# Domino_Pi_No_Teardrop.net
KiCad netlist of a schematic drawn in EAGLE
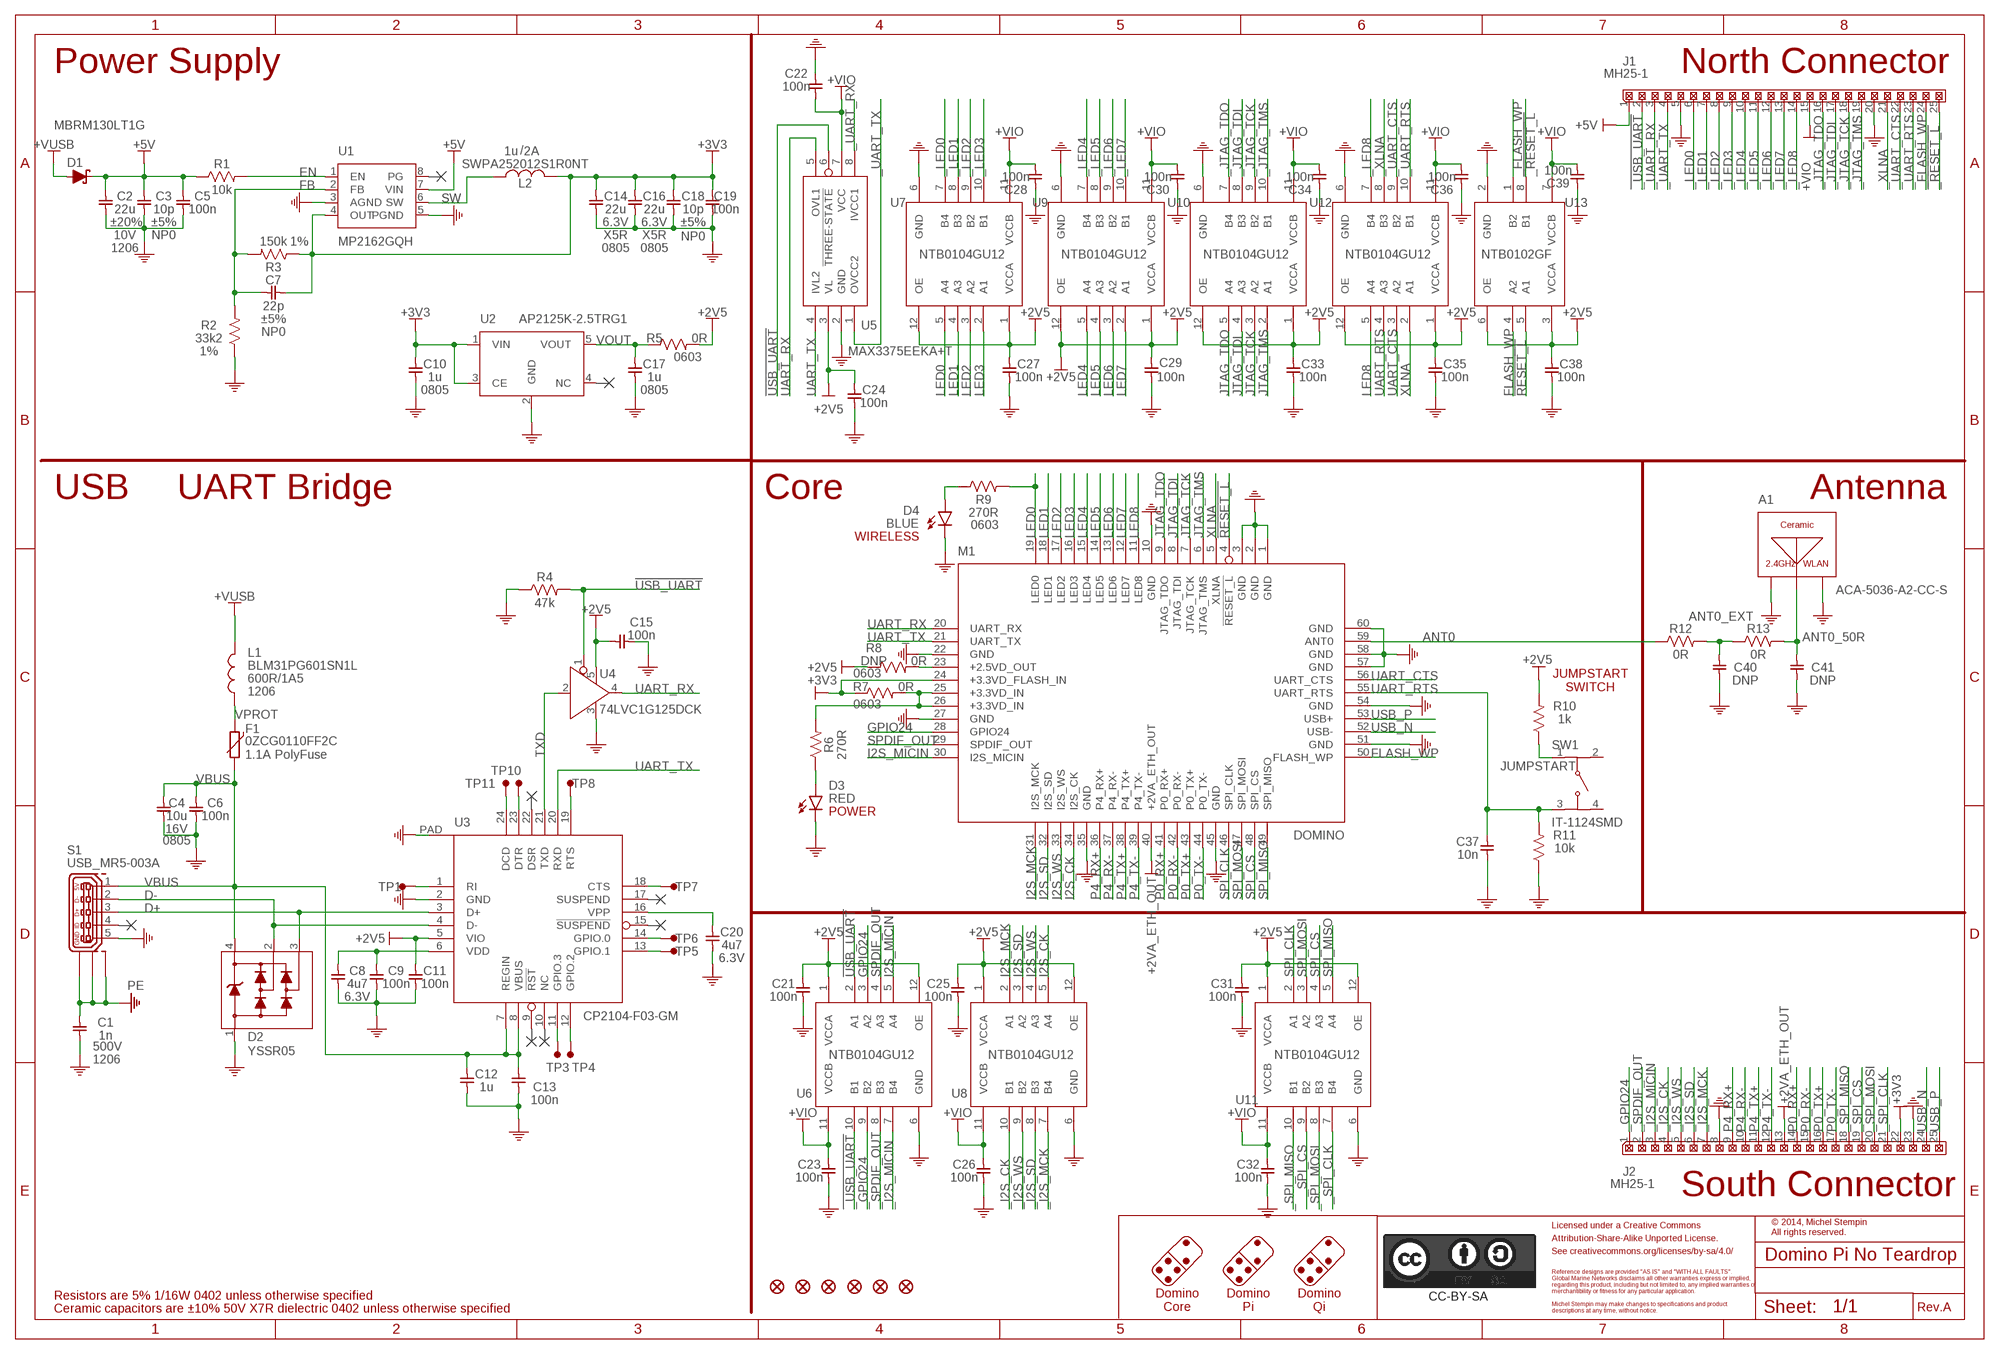
[diagram p0: schematic, sheet 1]

(export (version "E")
  (design (tool "Eeschema 10.0.6"))
  (components
    (comp (ref "A1")
      (value "ACA-5036-A2-CC-S")
      (footprint "eagle-import:ACA-5036-A2-CC-S")
      (libsource (lib "eagle-import") (part "ACA-5036-A2-CC-S"))
    )
    (comp (ref "C1")
      (value "1n")
      (footprint "eagle-import:C1206")
      (fields
        (field (name "SIZE") "1206")
        (field (name "PARTNO") "C1206_1n_X7R_10%_CER_500V")
        (field (name "VOLT") "500V")
      )
      (libsource (lib "eagle-import") (part "CAP_1206"))
    )
    (comp (ref "C2")
      (value "22u")
      (footprint "eagle-import:C1206")
      (fields
        (field (name "SIZE") "1206")
        (field (name "PARTNO") "C1206_22u_X7R_20%_CER_10V")
        (field (name "TOL") "±20%")
        (field (name "VOLT") "10V")
      )
      (libsource (lib "eagle-import") (part "CAP_1206"))
    )
    (comp (ref "C3")
      (value "10p")
      (footprint "eagle-import:C0402")
      (fields
        (field (name "PARTNO") "C0402_10p_NP0_5%_CER_50V")
        (field (name "TC") "NP0")
        (field (name "TOL") "±5%")
      )
      (libsource (lib "eagle-import") (part "CAP_0402"))
    )
    (comp (ref "C4")
      (value "10u")
      (footprint "eagle-import:C0805")
      (fields
        (field (name "SIZE") "0805")
        (field (name "PARTNO") "C0805_10u_X7R_10%_CER_16V")
        (field (name "VOLT") "16V")
      )
      (libsource (lib "eagle-import") (part "CAP_0805"))
    )
    (comp (ref "C5")
      (value "100n")
      (footprint "eagle-import:C0402")
      (fields (field (name "PARTNO") "C0402_100n_X7R_10%_CER_50V"))
      (libsource (lib "eagle-import") (part "CAP_0402"))
    )
    (comp (ref "C6")
      (value "100n")
      (footprint "eagle-import:C0402")
      (fields (field (name "PARTNO") "C0402_100n_X7R_10%_CER_50V"))
      (libsource (lib "eagle-import") (part "CAP_0402"))
    )
    (comp (ref "C7")
      (value "22p")
      (footprint "eagle-import:C0402")
      (fields
        (field (name "PARTNO") "C0402_22p_NP0_5%_CER_50V")
        (field (name "TC") "NP0")
        (field (name "TOL") "±5%")
      )
      (libsource (lib "eagle-import") (part "CAP_0402"))
    )
    (comp (ref "C8")
      (value "4u7")
      (footprint "eagle-import:C0402")
      (fields (field (name "PARTNO") "C0402_4u7_X7R_10%_CER_6V3") (field (name "VOLT") "6.3V"))
      (libsource (lib "eagle-import") (part "CAP_0402"))
    )
    (comp (ref "C9")
      (value "100n")
      (footprint "eagle-import:C0402")
      (fields (field (name "PARTNO") "C0402_100n_X7R_10%_CER_50V"))
      (libsource (lib "eagle-import") (part "CAP_0402"))
    )
    (comp (ref "C10")
      (value "1u")
      (footprint "eagle-import:C0805")
      (fields (field (name "SIZE") "0805") (field (name "PARTNO") "C0805_1u_X7R_10%_CER_50V"))
      (libsource (lib "eagle-import") (part "CAP_0805"))
    )
    (comp (ref "C11")
      (value "100n")
      (footprint "eagle-import:C0402")
      (fields (field (name "PARTNO") "C0402_100n_X7R_10%_CER_50V"))
      (libsource (lib "eagle-import") (part "CAP_0402"))
    )
    (comp (ref "C12")
      (value "1u")
      (footprint "eagle-import:C0402")
      (fields (field (name "PARTNO") "C0402_1u_X7R_10%_CER_50V"))
      (libsource (lib "eagle-import") (part "CAP_0402"))
    )
    (comp (ref "C13")
      (value "100n")
      (footprint "eagle-import:C0402")
      (fields (field (name "PARTNO") "C0402_100n_X7R_10%_CER_50V"))
      (libsource (lib "eagle-import") (part "CAP_0402"))
    )
    (comp (ref "C14")
      (value "22u")
      (footprint "eagle-import:C0805")
      (fields
        (field (name "SIZE") "0805")
        (field (name "PARTNO") "C0805_22u_X5R_20%_CER_6V3")
        (field (name "TC") "X5R")
        (field (name "VOLT") "6.3V")
      )
      (libsource (lib "eagle-import") (part "CAP_0805"))
    )
    (comp (ref "C15")
      (value "100n")
      (footprint "eagle-import:C0402")
      (fields (field (name "PARTNO") "C0402_100n_X7R_10%_CER_50V"))
      (libsource (lib "eagle-import") (part "CAP_0402"))
    )
    (comp (ref "C16")
      (value "22u")
      (footprint "eagle-import:C0805")
      (fields
        (field (name "SIZE") "0805")
        (field (name "PARTNO") "C0805_22u_X5R_20%_CER_6V3")
        (field (name "TC") "X5R")
        (field (name "VOLT") "6.3V")
      )
      (libsource (lib "eagle-import") (part "CAP_0805"))
    )
    (comp (ref "C17")
      (value "1u")
      (footprint "eagle-import:C0805")
      (fields (field (name "SIZE") "0805") (field (name "PARTNO") "C0805_1u_X7R_10%_CER_50V"))
      (libsource (lib "eagle-import") (part "CAP_0805"))
    )
    (comp (ref "C18")
      (value "10p")
      (footprint "eagle-import:C0402")
      (fields
        (field (name "PARTNO") "C0402_10p_NP0_5%_CER_50V")
        (field (name "TC") "NP0")
        (field (name "TOL") "±5%")
      )
      (libsource (lib "eagle-import") (part "CAP_0402"))
    )
    (comp (ref "C19")
      (value "100n")
      (footprint "eagle-import:C0402")
      (fields (field (name "PARTNO") "C0402_100n_X7R_10%_CER_50V"))
      (libsource (lib "eagle-import") (part "CAP_0402"))
    )
    (comp (ref "C20")
      (value "4u7")
      (footprint "eagle-import:C0402")
      (fields (field (name "PARTNO") "C0402_4u7_X7R_10%_CER_6V3") (field (name "VOLT") "6.3V"))
      (libsource (lib "eagle-import") (part "CAP_0402"))
    )
    (comp (ref "C21")
      (value "100n")
      (footprint "eagle-import:C0402")
      (fields (field (name "PARTNO") "C0402_100n_X7R_10%_CER_50V"))
      (libsource (lib "eagle-import") (part "CAP_0402"))
    )
    (comp (ref "C22")
      (value "100n")
      (footprint "eagle-import:C0402")
      (fields (field (name "PARTNO") "C0402_100n_X7R_10%_CER_50V"))
      (libsource (lib "eagle-import") (part "CAP_0402"))
    )
    (comp (ref "C23")
      (value "100n")
      (footprint "eagle-import:C0402")
      (fields (field (name "PARTNO") "C0402_100n_X7R_10%_CER_50V"))
      (libsource (lib "eagle-import") (part "CAP_0402"))
    )
    (comp (ref "C24")
      (value "100n")
      (footprint "eagle-import:C0402")
      (fields (field (name "PARTNO") "C0402_100n_X7R_10%_CER_50V"))
      (libsource (lib "eagle-import") (part "CAP_0402"))
    )
    (comp (ref "C25")
      (value "100n")
      (footprint "eagle-import:C0402")
      (fields (field (name "PARTNO") "C0402_100n_X7R_10%_CER_50V"))
      (libsource (lib "eagle-import") (part "CAP_0402"))
    )
    (comp (ref "C26")
      (value "100n")
      (footprint "eagle-import:C0402")
      (fields (field (name "PARTNO") "C0402_100n_X7R_10%_CER_50V"))
      (libsource (lib "eagle-import") (part "CAP_0402"))
    )
    (comp (ref "C27")
      (value "100n")
      (footprint "eagle-import:C0402")
      (fields (field (name "PARTNO") "C0402_100n_X7R_10%_CER_50V"))
      (libsource (lib "eagle-import") (part "CAP_0402"))
    )
    (comp (ref "C28")
      (value "100n")
      (footprint "eagle-import:C0402")
      (fields (field (name "PARTNO") "C0402_100n_X7R_10%_CER_50V"))
      (libsource (lib "eagle-import") (part "CAP_0402"))
    )
    (comp (ref "C29")
      (value "100n")
      (footprint "eagle-import:C0402")
      (fields (field (name "PARTNO") "C0402_100n_X7R_10%_CER_50V"))
      (libsource (lib "eagle-import") (part "CAP_0402"))
    )
    (comp (ref "C30")
      (value "100n")
      (footprint "eagle-import:C0402")
      (fields (field (name "PARTNO") "C0402_100n_X7R_10%_CER_50V"))
      (libsource (lib "eagle-import") (part "CAP_0402"))
    )
    (comp (ref "C31")
      (value "100n")
      (footprint "eagle-import:C0402")
      (fields (field (name "PARTNO") "C0402_100n_X7R_10%_CER_50V"))
      (libsource (lib "eagle-import") (part "CAP_0402"))
    )
    (comp (ref "C32")
      (value "100n")
      (footprint "eagle-import:C0402")
      (fields (field (name "PARTNO") "C0402_100n_X7R_10%_CER_50V"))
      (libsource (lib "eagle-import") (part "CAP_0402"))
    )
    (comp (ref "C33")
      (value "100n")
      (footprint "eagle-import:C0402")
      (fields (field (name "PARTNO") "C0402_100n_X7R_10%_CER_50V"))
      (libsource (lib "eagle-import") (part "CAP_0402"))
    )
    (comp (ref "C34")
      (value "100n")
      (footprint "eagle-import:C0402")
      (fields (field (name "PARTNO") "C0402_100n_X7R_10%_CER_50V"))
      (libsource (lib "eagle-import") (part "CAP_0402"))
    )
    (comp (ref "C35")
      (value "100n")
      (footprint "eagle-import:C0402")
      (fields (field (name "PARTNO") "C0402_100n_X7R_10%_CER_50V"))
      (libsource (lib "eagle-import") (part "CAP_0402"))
    )
    (comp (ref "C36")
      (value "100n")
      (footprint "eagle-import:C0402")
      (fields (field (name "PARTNO") "C0402_100n_X7R_10%_CER_50V"))
      (libsource (lib "eagle-import") (part "CAP_0402"))
    )
    (comp (ref "C37")
      (value "10n")
      (footprint "eagle-import:C0402")
      (fields (field (name "PARTNO") "C0402_10n_X7R_10%_CER_50V"))
      (libsource (lib "eagle-import") (part "CAP_0402"))
    )
    (comp (ref "C38")
      (value "100n")
      (footprint "eagle-import:C0402")
      (fields (field (name "PARTNO") "C0402_100n_X7R_10%_CER_50V"))
      (libsource (lib "eagle-import") (part "CAP_0402"))
    )
    (comp (ref "C39")
      (value "100n")
      (footprint "eagle-import:C0402")
      (fields (field (name "PARTNO") "C0402_100n_X7R_10%_CER_50V"))
      (libsource (lib "eagle-import") (part "CAP_0402"))
    )
    (comp (ref "C40")
      (value "DNP")
      (footprint "eagle-import:C0402")
      (fields (field (name "PARTNO") "C0402_DNP"))
      (libsource (lib "eagle-import") (part "CAP_0402"))
    )
    (comp (ref "C41")
      (value "DNP")
      (footprint "eagle-import:C0402")
      (fields (field (name "PARTNO") "C0402_DNP"))
      (libsource (lib "eagle-import") (part "CAP_0402"))
    )
    (comp (ref "CC-BY-SA")
      (value "CC-BY-SA_LOGO")
      (footprint "eagle-import:CC-BY-SA_LOGO")
      (libsource (lib "eagle-import") (part "CC-BY-SA_LOGO"))
    )
    (comp (ref "D1")
      (value "MBRM130LT1G")
      (footprint "eagle-import:DO-216AA")
      (libsource (lib "eagle-import") (part "MBRM130LT1G"))
    )
    (comp (ref "D2")
      (value "YSSR05")
      (footprint "eagle-import:SOT143B")
      (libsource (lib "eagle-import") (part "YSSR05"))
    )
    (comp (ref "D3")
      (value "RED")
      (footprint "eagle-import:LED0603")
      (fields (field (name "PARTNO") "LED0603-RED"))
      (libsource (lib "eagle-import") (part "LED_0603"))
    )
    (comp (ref "D4")
      (value "BLUE")
      (footprint "eagle-import:LED0603")
      (fields (field (name "PARTNO") "LED0603-BLUE"))
      (libsource (lib "eagle-import") (part "LED_0603"))
    )
    (comp (ref "F1")
      (value "0ZCG0110FF2C")
      (footprint "eagle-import:PTC1812")
      (fields (field (name "RATE") "1.1A"))
      (libsource (lib "eagle-import") (part "0ZCG0110FF2C"))
    )
    (comp (ref "F2")
      (value "FIDUCIAL")
      (footprint "eagle-import:FIDUCIAL")
      (libsource (lib "eagle-import") (part "FIDUCIAL"))
    )
    (comp (ref "F3")
      (value "FIDUCIAL")
      (footprint "eagle-import:FIDUCIAL")
      (libsource (lib "eagle-import") (part "FIDUCIAL"))
    )
    (comp (ref "F4")
      (value "FIDUCIAL")
      (footprint "eagle-import:FIDUCIAL")
      (libsource (lib "eagle-import") (part "FIDUCIAL"))
    )
    (comp (ref "F5")
      (value "FIDUCIAL")
      (footprint "eagle-import:FIDUCIAL")
      (libsource (lib "eagle-import") (part "FIDUCIAL"))
    )
    (comp (ref "F6")
      (value "FIDUCIAL")
      (footprint "eagle-import:FIDUCIAL")
      (libsource (lib "eagle-import") (part "FIDUCIAL"))
    )
    (comp (ref "F7")
      (value "FIDUCIAL")
      (footprint "eagle-import:FIDUCIAL")
      (libsource (lib "eagle-import") (part "FIDUCIAL"))
    )
    (comp (ref "J1")
      (value "MH25-1")
      (footprint "eagle-import:MH25-1-0.1")
      (fields (field (name "PARTNO") "MH25-1-0.1"))
      (libsource (lib "eagle-import") (part "MH25-1"))
    )
    (comp (ref "J2")
      (value "MH25-1")
      (footprint "eagle-import:MH25-1-0.1")
      (fields (field (name "PARTNO") "MH25-1-0.1"))
      (libsource (lib "eagle-import") (part "MH25-1"))
    )
    (comp (ref "L1")
      (value "BLM31PG601SN1L")
      (footprint "eagle-import:FB1206")
      (fields (field (name "SIZE") "1206") (field (name "OPT") "600R/1A5"))
      (libsource (lib "eagle-import") (part "FB_1206"))
    )
    (comp (ref "L2")
      (value "SWPA252012S1R0NT")
      (footprint "eagle-import:SWPA252012S")
      (fields
        (field (name "INDUCTANCE") "1u")
        (field (name "RATE") "2A")
        (field (name "PARTNO") "SWPA252012SMT")
        (field (name "RATE_1") "2A")
      )
      (libsource (lib "eagle-import") (part "SWPA252012S?NT1R0"))
    )
    (comp (ref "M1")
      (value "DOMINO")
      (footprint "eagle-import:DOMINO")
      (fields (field (name "PARTNO") "DOMINO-CORE"))
      (libsource (lib "eagle-import") (part "DOMINO"))
    )
    (comp (ref "R1")
      (value "10k")
      (footprint "eagle-import:R0402")
      (fields (field (name "PARTNO") "R0402_10k_5%_62.5mW"))
      (libsource (lib "eagle-import") (part "RES_0402"))
    )
    (comp (ref "R2")
      (value "33k2")
      (footprint "eagle-import:R0402")
      (fields (field (name "PARTNO") "R0402_33k2_1%_62.5mW") (field (name "TOL") "1%"))
      (libsource (lib "eagle-import") (part "RES_0402"))
    )
    (comp (ref "R3")
      (value "150k")
      (footprint "eagle-import:R0402")
      (fields (field (name "PARTNO") "R0402_150k_1%_62.5mW") (field (name "TOL") "1%"))
      (libsource (lib "eagle-import") (part "RES_0402"))
    )
    (comp (ref "R4")
      (value "47k")
      (footprint "eagle-import:R0402")
      (fields (field (name "PARTNO") "R0402_47k_5%_62.5mW"))
      (libsource (lib "eagle-import") (part "RES_0402"))
    )
    (comp (ref "R5")
      (value "0R")
      (footprint "eagle-import:R0603")
      (fields (field (name "SIZE") "0603") (field (name "PARTNO") "R0603_0R_5%_125mW"))
      (libsource (lib "eagle-import") (part "RES_0603"))
    )
    (comp (ref "R6")
      (value "270R")
      (footprint "eagle-import:R0402")
      (fields (field (name "PARTNO") "R0603_270R_5%_125mW"))
      (libsource (lib "eagle-import") (part "RES_0402"))
    )
    (comp (ref "R7")
      (value "0R")
      (footprint "eagle-import:R0603")
      (fields (field (name "SIZE") "0603") (field (name "PARTNO") "R0603_0R_5%_125mW"))
      (libsource (lib "eagle-import") (part "RES_0603"))
    )
    (comp (ref "R8")
      (value "0R")
      (footprint "eagle-import:R0603")
      (fields (field (name "SIZE") "0603") (field (name "PARTNO") "R0603_0R_5%_125mW"))
      (libsource (lib "eagle-import") (part "RES_0603"))
    )
    (comp (ref "R9")
      (value "270R")
      (footprint "eagle-import:R0603")
      (fields (field (name "SIZE") "0603") (field (name "PARTNO") "R0603_270R_5%_125mW"))
      (libsource (lib "eagle-import") (part "RES_0603"))
    )
    (comp (ref "R10")
      (value "1k")
      (footprint "eagle-import:R0402")
      (fields (field (name "PARTNO") "R0402_1k_5%_62.5mW"))
      (libsource (lib "eagle-import") (part "RES_0402"))
    )
    (comp (ref "R11")
      (value "10k")
      (footprint "eagle-import:R0402")
      (fields (field (name "PARTNO") "R0402_10k_5%_62.5mW"))
      (libsource (lib "eagle-import") (part "RES_0402"))
    )
    (comp (ref "R12")
      (value "0R")
      (footprint "eagle-import:R0402")
      (fields (field (name "PARTNO") "R0402_0R_5%_62.5mW"))
      (libsource (lib "eagle-import") (part "RES_0402"))
    )
    (comp (ref "R13")
      (value "0R")
      (footprint "eagle-import:R0402")
      (fields (field (name "PARTNO") "R0402_0R_5%_62.5mW"))
      (libsource (lib "eagle-import") (part "RES_0402"))
    )
    (comp (ref "S1")
      (value "USB_MR5-003A")
      (footprint "eagle-import:USB_MR5-003A")
      (fields (field (name "PARTNO") "USB MR5-003A"))
      (libsource (lib "eagle-import") (part "USB_MR5-003A"))
    )
    (comp (ref "SW1")
      (value "IT-1124SMD")
      (footprint "eagle-import:IT-1124SMD")
      (libsource (lib "eagle-import") (part "IT-1124SMD"))
    )
    (comp (ref "TP1")
      (value "TEST_PAD")
      (footprint "eagle-import:TEST_PAD")
      (libsource (lib "eagle-import") (part "TEST_PAD"))
    )
    (comp (ref "TP3")
      (value "TEST_PAD")
      (footprint "eagle-import:TEST_PAD")
      (libsource (lib "eagle-import") (part "TEST_PAD"))
    )
    (comp (ref "TP4")
      (value "TEST_PAD")
      (footprint "eagle-import:TEST_PAD")
      (libsource (lib "eagle-import") (part "TEST_PAD"))
    )
    (comp (ref "TP5")
      (value "TEST_PAD")
      (footprint "eagle-import:TEST_PAD")
      (libsource (lib "eagle-import") (part "TEST_PAD"))
    )
    (comp (ref "TP6")
      (value "TEST_PAD")
      (footprint "eagle-import:TEST_PAD")
      (libsource (lib "eagle-import") (part "TEST_PAD"))
    )
    (comp (ref "TP7")
      (value "TEST_PAD")
      (footprint "eagle-import:TEST_PAD")
      (libsource (lib "eagle-import") (part "TEST_PAD"))
    )
    (comp (ref "TP8")
      (value "TEST_PAD")
      (footprint "eagle-import:TEST_PAD")
      (libsource (lib "eagle-import") (part "TEST_PAD"))
    )
    (comp (ref "TP10")
      (value "TEST_PAD")
      (footprint "eagle-import:TEST_PAD")
      (libsource (lib "eagle-import") (part "TEST_PAD"))
    )
    (comp (ref "TP11")
      (value "TEST_PAD")
      (footprint "eagle-import:TEST_PAD")
      (libsource (lib "eagle-import") (part "TEST_PAD"))
    )
    (comp (ref "U1")
      (value "MP2162GQH")
      (footprint "eagle-import:QFN-8_2X1.5")
      (libsource (lib "eagle-import") (part "MP2162GQH"))
    )
    (comp (ref "U2")
      (value "AP2125K-2.5TRG1")
      (footprint "eagle-import:SOT23-5")
      (libsource (lib "eagle-import") (part "AP2125?K-2.5TRG1"))
    )
    (comp (ref "U3")
      (value "CP2104-F03-GM")
      (footprint "eagle-import:QFN-25_4X4")
      (libsource (lib "eagle-import") (part "CP2104-F03-GM"))
    )
    (comp (ref "U4")
      (value "74LVC1G125DCK")
      (footprint "eagle-import:SC70")
      (fields (field (name "PARTNO") "74LVC1G125DCK "))
      (libsource (lib "eagle-import") (part "741G125DCKLVC"))
    )
    (comp (ref "U5")
      (value "MAX3375EEKA+T")
      (footprint "eagle-import:SOT23-8")
      (libsource (lib "eagle-import") (part "MAX3375EEKA+T"))
    )
    (comp (ref "U6")
      (value "NTB0104GU12")
      (footprint "eagle-import:XQFN-12")
      (libsource (lib "eagle-import") (part "NTB0104GU12"))
    )
    (comp (ref "U7")
      (value "NTB0104GU12")
      (footprint "eagle-import:XQFN-12")
      (libsource (lib "eagle-import") (part "NTB0104GU12"))
    )
    (comp (ref "U8")
      (value "NTB0104GU12")
      (footprint "eagle-import:XQFN-12")
      (libsource (lib "eagle-import") (part "NTB0104GU12"))
    )
    (comp (ref "U9")
      (value "NTB0104GU12")
      (footprint "eagle-import:XQFN-12")
      (libsource (lib "eagle-import") (part "NTB0104GU12"))
    )
    (comp (ref "U10")
      (value "NTB0104GU12")
      (footprint "eagle-import:XQFN-12")
      (libsource (lib "eagle-import") (part "NTB0104GU12"))
    )
    (comp (ref "U11")
      (value "NTB0104GU12")
      (footprint "eagle-import:XQFN-12")
      (libsource (lib "eagle-import") (part "NTB0104GU12"))
    )
    (comp (ref "U12")
      (value "NTB0104GU12")
      (footprint "eagle-import:XQFN-12")
      (libsource (lib "eagle-import") (part "NTB0104GU12"))
    )
    (comp (ref "U13")
      (value "NTB0102GF")
      (footprint "eagle-import:SOT1089")
      (libsource (lib "eagle-import") (part "NTB0102GF"))
    )
  )
  (nets
    (net (code "1") (name "+2V5") (class "Default")
      (node (ref "C11") (pin "1") (pinfunction "1_1") (pintype "passive"))
      (node (ref "C15") (pin "2") (pinfunction "2_2") (pintype "passive"))
      (node (ref "C21") (pin "1") (pinfunction "1_1") (pintype "passive"))
      (node (ref "C24") (pin "2") (pinfunction "2_2") (pintype "passive"))
      (node (ref "C25") (pin "1") (pinfunction "1_1") (pintype "passive"))
      (node (ref "C27") (pin "2") (pinfunction "2_2") (pintype "passive"))
      (node (ref "C29") (pin "2") (pinfunction "2_2") (pintype "passive"))
      (node (ref "C31") (pin "1") (pinfunction "1_1") (pintype "passive"))
      (node (ref "C33") (pin "2") (pinfunction "2_2") (pintype "passive"))
      (node (ref "C35") (pin "2") (pinfunction "2_2") (pintype "passive"))
      (node (ref "C38") (pin "2") (pinfunction "2_2") (pintype "passive"))
      (node (ref "R10") (pin "2") (pinfunction "2_2") (pintype "passive"))
      (node (ref "R5") (pin "2") (pinfunction "2_2") (pintype "passive"))
      (node (ref "R8") (pin "1") (pinfunction "1_1") (pintype "passive"))
      (node (ref "U10") (pin "1") (pinfunction "VCCA_1") (pintype "power_in"))
      (node (ref "U10") (pin "12") (pinfunction "OE_12") (pintype "input"))
      (node (ref "U11") (pin "1") (pinfunction "VCCA_1") (pintype "power_in"))
      (node (ref "U11") (pin "12") (pinfunction "OE_12") (pintype "input"))
      (node (ref "U12") (pin "1") (pinfunction "VCCA_1") (pintype "power_in"))
      (node (ref "U12") (pin "12") (pinfunction "OE_12") (pintype "input"))
      (node (ref "U13") (pin "3") (pinfunction "VCCA_3") (pintype "power_in"))
      (node (ref "U13") (pin "6") (pinfunction "OE_6") (pintype "input"))
      (node (ref "U3") (pin "5") (pinfunction "VIO_5") (pintype "power_in"))
      (node (ref "U4") (pin "5") (pinfunction "VCC_5") (pintype "power_in"))
      (node (ref "U5") (pin "3") (pinfunction "VL_3") (pintype "power_in"))
      (node (ref "U6") (pin "1") (pinfunction "VCCA_1") (pintype "power_in"))
      (node (ref "U6") (pin "12") (pinfunction "OE_12") (pintype "input"))
      (node (ref "U7") (pin "1") (pinfunction "VCCA_1") (pintype "power_in"))
      (node (ref "U7") (pin "12") (pinfunction "OE_12") (pintype "input"))
      (node (ref "U8") (pin "1") (pinfunction "VCCA_1") (pintype "power_in"))
      (node (ref "U8") (pin "12") (pinfunction "OE_12") (pintype "input"))
      (node (ref "U9") (pin "1") (pinfunction "VCCA_1") (pintype "power_in"))
      (node (ref "U9") (pin "12") (pinfunction "OE_12") (pintype "input"))
    )
    (net (code "2") (name "+2VA_ETH_OUT") (class "Default")
      (node (ref "J2") (pin "13") (pinfunction "13_13") (pintype "passive"))
      (node (ref "M1") (pin "40") (pinfunction "+2VA_ETH_OUT_40") (pintype "power_in"))
    )
    (net (code "3") (name "+3V3") (class "Default")
      (node (ref "C10") (pin "1") (pinfunction "1_1") (pintype "passive"))
      (node (ref "C14") (pin "1") (pinfunction "1_1") (pintype "passive"))
      (node (ref "C16") (pin "1") (pinfunction "1_1") (pintype "passive"))
      (node (ref "C18") (pin "1") (pinfunction "1_1") (pintype "passive"))
      (node (ref "C19") (pin "1") (pinfunction "1_1") (pintype "passive"))
      (node (ref "C7") (pin "2") (pinfunction "2_2") (pintype "passive"))
      (node (ref "J2") (pin "22") (pinfunction "22_22") (pintype "passive"))
      (node (ref "L2") (pin "2") (pinfunction "2_2") (pintype "passive"))
      (node (ref "M1") (pin "24") (pinfunction "+3.3VD_FLASH_IN_24") (pintype "power_in"))
      (node (ref "R3") (pin "1") (pinfunction "1_1") (pintype "passive"))
      (node (ref "R7") (pin "1") (pinfunction "1_1") (pintype "passive"))
      (node (ref "U1") (pin "4") (pinfunction "OUT_4") (pintype "power_in"))
      (node (ref "U2") (pin "1") (pinfunction "VIN_1") (pintype "power_in"))
      (node (ref "U2") (pin "3") (pinfunction "CE_3") (pintype "input"))
    )
    (net (code "4") (name "+5V") (class "Default")
      (node (ref "C2") (pin "1") (pinfunction "1_1") (pintype "passive"))
      (node (ref "C3") (pin "1") (pinfunction "1_1") (pintype "passive"))
      (node (ref "C5") (pin "1") (pinfunction "1_1") (pintype "passive"))
      (node (ref "D1") (pin "1") (pinfunction "C_1") (pintype "passive"))
      (node (ref "J1") (pin "1") (pinfunction "1_1") (pintype "passive"))
      (node (ref "R1") (pin "1") (pinfunction "1_1") (pintype "passive"))
      (node (ref "U1") (pin "7") (pinfunction "VIN_7") (pintype "power_in"))
    )
    (net (code "5") (name "+VIO") (class "Default")
      (node (ref "C22") (pin "1") (pinfunction "1_1") (pintype "passive"))
      (node (ref "C23") (pin "1") (pinfunction "1_1") (pintype "passive"))
      (node (ref "C26") (pin "1") (pinfunction "1_1") (pintype "passive"))
      (node (ref "C28") (pin "1") (pinfunction "1_1") (pintype "passive"))
      (node (ref "C30") (pin "1") (pinfunction "1_1") (pintype "passive"))
      (node (ref "C32") (pin "1") (pinfunction "1_1") (pintype "passive"))
      (node (ref "C34") (pin "1") (pinfunction "1_1") (pintype "passive"))
      (node (ref "C36") (pin "1") (pinfunction "1_1") (pintype "passive"))
      (node (ref "C39") (pin "1") (pinfunction "1_1") (pintype "passive"))
      (node (ref "J1") (pin "15") (pinfunction "15_15") (pintype "passive"))
      (node (ref "U10") (pin "11") (pinfunction "VCCB_11") (pintype "power_in"))
      (node (ref "U11") (pin "11") (pinfunction "VCCB_11") (pintype "power_in"))
      (node (ref "U12") (pin "11") (pinfunction "VCCB_11") (pintype "power_in"))
      (node (ref "U13") (pin "7") (pinfunction "VCCB_7") (pintype "power_in"))
      (node (ref "U5") (pin "7") (pinfunction "VCC_7") (pintype "power_in"))
      (node (ref "U6") (pin "11") (pinfunction "VCCB_11") (pintype "power_in"))
      (node (ref "U7") (pin "11") (pinfunction "VCCB_11") (pintype "power_in"))
      (node (ref "U8") (pin "11") (pinfunction "VCCB_11") (pintype "power_in"))
      (node (ref "U9") (pin "11") (pinfunction "VCCB_11") (pintype "power_in"))
    )
    (net (code "6") (name "+VUSB") (class "Default")
      (node (ref "D1") (pin "2") (pinfunction "A_2") (pintype "passive"))
      (node (ref "L1") (pin "1") (pinfunction "1_1") (pintype "passive"))
    )
    (net (code "7") (name "/ANT0") (class "Default")
      (node (ref "M1") (pin "59") (pinfunction "ANT0_59") (pintype "passive"))
      (node (ref "R12") (pin "1") (pinfunction "1_1") (pintype "passive"))
    )
    (net (code "8") (name "/ANT0_50R") (class "Default")
      (node (ref "A1") (pin "FEED") (pinfunction "A_FEED") (pintype "passive"))
      (node (ref "C41") (pin "1") (pinfunction "1_1") (pintype "passive"))
      (node (ref "R13") (pin "2") (pinfunction "2_2") (pintype "passive"))
    )
    (net (code "9") (name "/ANT0_EXT") (class "Default")
      (node (ref "C40") (pin "1") (pinfunction "1_1") (pintype "passive"))
      (node (ref "R12") (pin "2") (pinfunction "2_2") (pintype "passive"))
      (node (ref "R13") (pin "1") (pinfunction "1_1") (pintype "passive"))
    )
    (net (code "10") (name "/D+") (class "Default")
      (node (ref "D2") (pin "3") (pinfunction "P$3_3") (pintype "passive"))
      (node (ref "S1") (pin "3") (pinfunction "3_3") (pintype "passive"))
      (node (ref "U3") (pin "3") (pinfunction "D+_3") (pintype "passive"))
    )
    (net (code "11") (name "/D-") (class "Default")
      (node (ref "D2") (pin "2") (pinfunction "P$2_2") (pintype "passive"))
      (node (ref "S1") (pin "2") (pinfunction "2_2") (pintype "passive"))
      (node (ref "U3") (pin "4") (pinfunction "D-_4") (pintype "passive"))
    )
    (net (code "12") (name "/EN") (class "Default")
      (node (ref "R1") (pin "2") (pinfunction "2_2") (pintype "passive"))
      (node (ref "U1") (pin "1") (pinfunction "EN_1") (pintype "input"))
    )
    (net (code "13") (name "/FB") (class "Default")
      (node (ref "C7") (pin "1") (pinfunction "1_1") (pintype "passive"))
      (node (ref "R2") (pin "2") (pinfunction "2_2") (pintype "passive"))
      (node (ref "R3") (pin "2") (pinfunction "2_2") (pintype "passive"))
      (node (ref "U1") (pin "2") (pinfunction "FB_2") (pintype "passive"))
    )
    (net (code "14") (name "/FLASH_WP") (class "Default")
      (node (ref "M1") (pin "50") (pinfunction "FLASH_WP_50") (pintype "bidirectional"))
      (node (ref "U13") (pin "4") (pinfunction "A2_4") (pintype "bidirectional"))
    )
    (net (code "15") (name "/GPIO24") (class "Default")
      (node (ref "M1") (pin "28") (pinfunction "GPIO24_28") (pintype "bidirectional"))
      (node (ref "U6") (pin "3") (pinfunction "A2_3") (pintype "bidirectional"))
    )
    (net (code "16") (name "/I2S_CK") (class "Default")
      (node (ref "M1") (pin "34") (pinfunction "I2S_CK_34") (pintype "bidirectional"))
      (node (ref "U8") (pin "5") (pinfunction "A4_5") (pintype "bidirectional"))
    )
    (net (code "17") (name "/I2S_MCK") (class "Default")
      (node (ref "M1") (pin "31") (pinfunction "I2S_MCK_31") (pintype "bidirectional"))
      (node (ref "U8") (pin "2") (pinfunction "A1_2") (pintype "bidirectional"))
    )
    (net (code "18") (name "/I2S_MICIN") (class "Default")
      (node (ref "M1") (pin "30") (pinfunction "I2S_MICIN_30") (pintype "bidirectional"))
      (node (ref "U6") (pin "5") (pinfunction "A4_5") (pintype "bidirectional"))
    )
    (net (code "19") (name "/I2S_SD") (class "Default")
      (node (ref "M1") (pin "32") (pinfunction "I2S_SD_32") (pintype "bidirectional"))
      (node (ref "U8") (pin "3") (pinfunction "A2_3") (pintype "bidirectional"))
    )
    (net (code "20") (name "/I2S_WS") (class "Default")
      (node (ref "M1") (pin "33") (pinfunction "I2S_WS_33") (pintype "bidirectional"))
      (node (ref "U8") (pin "4") (pinfunction "A3_4") (pintype "bidirectional"))
    )
    (net (code "21") (name "/JTAG_TCK") (class "Default")
      (node (ref "M1") (pin "7") (pinfunction "JTAG_TCK_7") (pintype "bidirectional"))
      (node (ref "U10") (pin "3") (pinfunction "A2_3") (pintype "bidirectional"))
    )
    (net (code "22") (name "/JTAG_TDI") (class "Default")
      (node (ref "M1") (pin "8") (pinfunction "JTAG_TDI_8") (pintype "bidirectional"))
      (node (ref "U10") (pin "4") (pinfunction "A3_4") (pintype "bidirectional"))
    )
    (net (code "23") (name "/JTAG_TDO") (class "Default")
      (node (ref "M1") (pin "9") (pinfunction "JTAG_TDO_9") (pintype "bidirectional"))
      (node (ref "U10") (pin "5") (pinfunction "A4_5") (pintype "bidirectional"))
    )
    (net (code "24") (name "/JTAG_TMS") (class "Default")
      (node (ref "M1") (pin "6") (pinfunction "JTAG_TMS_6") (pintype "bidirectional"))
      (node (ref "U10") (pin "2") (pinfunction "A1_2") (pintype "bidirectional"))
    )
    (net (code "25") (name "/JUMPSTART") (class "Default")
      (node (ref "R10") (pin "1") (pinfunction "1_1") (pintype "passive"))
      (node (ref "SW1") (pin "1") (pinfunction "1_1") (pintype "passive"))
    )
    (net (code "26") (name "/LED0") (class "Default")
      (node (ref "M1") (pin "19") (pinfunction "LED0_19") (pintype "bidirectional"))
      (node (ref "R9") (pin "2") (pinfunction "2_2") (pintype "passive"))
      (node (ref "U7") (pin "5") (pinfunction "A4_5") (pintype "bidirectional"))
    )
    (net (code "27") (name "/LED1") (class "Default")
      (node (ref "M1") (pin "18") (pinfunction "LED1_18") (pintype "bidirectional"))
      (node (ref "U7") (pin "4") (pinfunction "A3_4") (pintype "bidirectional"))
    )
    (net (code "28") (name "/LED2") (class "Default")
      (node (ref "M1") (pin "17") (pinfunction "LED2_17") (pintype "bidirectional"))
      (node (ref "U7") (pin "3") (pinfunction "A2_3") (pintype "bidirectional"))
    )
    (net (code "29") (name "/LED3") (class "Default")
      (node (ref "M1") (pin "16") (pinfunction "LED3_16") (pintype "bidirectional"))
      (node (ref "U7") (pin "2") (pinfunction "A1_2") (pintype "bidirectional"))
    )
    (net (code "30") (name "/LED4") (class "Default")
      (node (ref "M1") (pin "15") (pinfunction "LED4_15") (pintype "bidirectional"))
      (node (ref "U9") (pin "5") (pinfunction "A4_5") (pintype "bidirectional"))
    )
    (net (code "31") (name "/LED5") (class "Default")
      (node (ref "M1") (pin "14") (pinfunction "LED5_14") (pintype "bidirectional"))
      (node (ref "U9") (pin "4") (pinfunction "A3_4") (pintype "bidirectional"))
    )
    (net (code "32") (name "/LED6") (class "Default")
      (node (ref "M1") (pin "13") (pinfunction "LED6_13") (pintype "bidirectional"))
      (node (ref "U9") (pin "3") (pinfunction "A2_3") (pintype "bidirectional"))
    )
    (net (code "33") (name "/LED7") (class "Default")
      (node (ref "M1") (pin "12") (pinfunction "LED7_12") (pintype "bidirectional"))
      (node (ref "U9") (pin "2") (pinfunction "A1_2") (pintype "bidirectional"))
    )
    (net (code "34") (name "/LED8") (class "Default")
      (node (ref "M1") (pin "11") (pinfunction "LED8_11") (pintype "bidirectional"))
      (node (ref "U12") (pin "5") (pinfunction "A4_5") (pintype "bidirectional"))
    )
    (net (code "35") (name "/P0_RX+") (class "Default")
      (node (ref "J2") (pin "14") (pinfunction "14_14") (pintype "passive"))
      (node (ref "M1") (pin "41") (pinfunction "P0_RX+_41") (pintype "passive"))
    )
    (net (code "36") (name "/P0_RX-") (class "Default")
      (node (ref "J2") (pin "15") (pinfunction "15_15") (pintype "passive"))
      (node (ref "M1") (pin "42") (pinfunction "P0_RX-_42") (pintype "passive"))
    )
    (net (code "37") (name "/P0_TX+") (class "Default")
      (node (ref "J2") (pin "16") (pinfunction "16_16") (pintype "passive"))
      (node (ref "M1") (pin "43") (pinfunction "P0_TX+_43") (pintype "passive"))
    )
    (net (code "38") (name "/P0_TX-") (class "Default")
      (node (ref "J2") (pin "17") (pinfunction "17_17") (pintype "passive"))
      (node (ref "M1") (pin "44") (pinfunction "P0_TX-_44") (pintype "passive"))
    )
    (net (code "39") (name "/P4_RX+") (class "Default")
      (node (ref "J2") (pin "9") (pinfunction "9_9") (pintype "passive"))
      (node (ref "M1") (pin "36") (pinfunction "P4_RX+_36") (pintype "passive"))
    )
    (net (code "40") (name "/P4_RX-") (class "Default")
      (node (ref "J2") (pin "10") (pinfunction "10_10") (pintype "passive"))
      (node (ref "M1") (pin "37") (pinfunction "P4_RX-_37") (pintype "passive"))
    )
    (net (code "41") (name "/P4_TX+") (class "Default")
      (node (ref "J2") (pin "11") (pinfunction "11_11") (pintype "passive"))
      (node (ref "M1") (pin "38") (pinfunction "P4_TX+_38") (pintype "passive"))
    )
    (net (code "42") (name "/P4_TX-") (class "Default")
      (node (ref "J2") (pin "12") (pinfunction "12_12") (pintype "passive"))
      (node (ref "M1") (pin "39") (pinfunction "P4_TX-_39") (pintype "passive"))
    )
    (net (code "43") (name "/SPDIF_OUT") (class "Default")
      (node (ref "M1") (pin "29") (pinfunction "SPDIF_OUT_29") (pintype "bidirectional"))
      (node (ref "U6") (pin "4") (pinfunction "A3_4") (pintype "bidirectional"))
    )
    (net (code "44") (name "/SPI_CLK") (class "Default")
      (node (ref "M1") (pin "46") (pinfunction "SPI_CLK_46") (pintype "bidirectional"))
      (node (ref "U11") (pin "2") (pinfunction "A1_2") (pintype "bidirectional"))
    )
    (net (code "45") (name "/SPI_CS") (class "Default")
      (node (ref "M1") (pin "48") (pinfunction "SPI_CS_48") (pintype "bidirectional"))
      (node (ref "U11") (pin "4") (pinfunction "A3_4") (pintype "bidirectional"))
    )
    (net (code "46") (name "/SPI_MISO") (class "Default")
      (node (ref "M1") (pin "49") (pinfunction "SPI_MISO_49") (pintype "bidirectional"))
      (node (ref "U11") (pin "5") (pinfunction "A4_5") (pintype "bidirectional"))
    )
    (net (code "47") (name "/SPI_MOSI") (class "Default")
      (node (ref "M1") (pin "47") (pinfunction "SPI_MOSI_47") (pintype "bidirectional"))
      (node (ref "U11") (pin "3") (pinfunction "A2_3") (pintype "bidirectional"))
    )
    (net (code "48") (name "/SW") (class "Default")
      (node (ref "L2") (pin "1") (pinfunction "1_1") (pintype "passive"))
      (node (ref "U1") (pin "6") (pinfunction "SW_6") (pintype "passive"))
    )
    (net (code "49") (name "/TXD") (class "Default")
      (node (ref "U3") (pin "21") (pinfunction "TXD_21") (pintype "output"))
      (node (ref "U4") (pin "2") (pinfunction "A_2") (pintype "input"))
    )
    (net (code "50") (name "/UART_CTS") (class "Default")
      (node (ref "M1") (pin "56") (pinfunction "UART_CTS_56") (pintype "bidirectional"))
      (node (ref "U12") (pin "3") (pinfunction "A2_3") (pintype "bidirectional"))
    )
    (net (code "51") (name "/UART_RTS") (class "Default")
      (node (ref "C37") (pin "1") (pinfunction "1_1") (pintype "passive"))
      (node (ref "M1") (pin "55") (pinfunction "UART_RTS_55") (pintype "bidirectional"))
      (node (ref "R11") (pin "2") (pinfunction "2_2") (pintype "passive"))
      (node (ref "SW1") (pin "3") (pinfunction "3_3") (pintype "passive"))
      (node (ref "U12") (pin "4") (pinfunction "A3_4") (pintype "bidirectional"))
    )
    (net (code "52") (name "/UART_RX") (class "Default")
      (node (ref "M1") (pin "20") (pinfunction "UART_RX_20") (pintype "bidirectional"))
      (node (ref "U4") (pin "4") (pinfunction "Y_4") (pintype "tri_state"))
      (node (ref "U5") (pin "5") (pinfunction "OVL1_5") (pintype "output"))
    )
    (net (code "53") (name "/UART_TX") (class "Default")
      (node (ref "M1") (pin "21") (pinfunction "UART_TX_21") (pintype "bidirectional"))
      (node (ref "U3") (pin "20") (pinfunction "RXD_20") (pintype "input"))
      (node (ref "U5") (pin "4") (pinfunction "IVL2_4") (pintype "input"))
    )
    (net (code "54") (name "/USB_N") (class "Default")
      (node (ref "J2") (pin "24") (pinfunction "24_24") (pintype "passive"))
      (node (ref "M1") (pin "52") (pinfunction "USB-_52") (pintype "passive"))
    )
    (net (code "55") (name "/USB_P") (class "Default")
      (node (ref "J2") (pin "25") (pinfunction "25_25") (pintype "passive"))
      (node (ref "M1") (pin "53") (pinfunction "USB+_53") (pintype "passive"))
    )
    (net (code "56") (name "/VBUS") (class "Default")
      (node (ref "C12") (pin "1") (pinfunction "1_1") (pintype "passive"))
      (node (ref "C13") (pin "1") (pinfunction "1_1") (pintype "passive"))
      (node (ref "C4") (pin "1") (pinfunction "1_1") (pintype "passive"))
      (node (ref "C6") (pin "1") (pinfunction "1_1") (pintype "passive"))
      (node (ref "D2") (pin "4") (pinfunction "P$4_4") (pintype "passive"))
      (node (ref "F1") (pin "2") (pinfunction "2_2") (pintype "passive"))
      (node (ref "S1") (pin "1") (pinfunction "1_1") (pintype "passive"))
      (node (ref "U3") (pin "7") (pinfunction "REGIN_7") (pintype "power_in"))
      (node (ref "U3") (pin "8") (pinfunction "VBUS_8") (pintype "input"))
    )
    (net (code "57") (name "/VOUT") (class "Default")
      (node (ref "C17") (pin "1") (pinfunction "1_1") (pintype "passive"))
      (node (ref "R5") (pin "1") (pinfunction "1_1") (pintype "passive"))
      (node (ref "U2") (pin "5") (pinfunction "VOUT_5") (pintype "power_in"))
    )
    (net (code "58") (name "/VPROT") (class "Default")
      (node (ref "F1") (pin "1") (pinfunction "1_1") (pintype "passive"))
      (node (ref "L1") (pin "2") (pinfunction "2_2") (pintype "passive"))
    )
    (net (code "59") (name "/XLNA") (class "Default")
      (node (ref "M1") (pin "5") (pinfunction "XLNA_5") (pintype "bidirectional"))
      (node (ref "U12") (pin "2") (pinfunction "A1_2") (pintype "bidirectional"))
    )
    (net (code "60") (name "/_FLASH_WP") (class "Default")
      (node (ref "J1") (pin "24") (pinfunction "24_24") (pintype "passive"))
      (node (ref "U13") (pin "1") (pinfunction "B2_1") (pintype "bidirectional"))
    )
    (net (code "61") (name "/_GPIO24") (class "Default")
      (node (ref "J2") (pin "1") (pinfunction "1_1") (pintype "passive"))
      (node (ref "U6") (pin "9") (pinfunction "B2_9") (pintype "bidirectional"))
    )
    (net (code "62") (name "/_I2S_CK") (class "Default")
      (node (ref "J2") (pin "4") (pinfunction "4_4") (pintype "passive"))
      (node (ref "U8") (pin "10") (pinfunction "B1_10") (pintype "bidirectional"))
    )
    (net (code "63") (name "/_I2S_MCK") (class "Default")
      (node (ref "J2") (pin "7") (pinfunction "7_7") (pintype "passive"))
      (node (ref "U8") (pin "7") (pinfunction "B4_7") (pintype "bidirectional"))
    )
    (net (code "64") (name "/_I2S_MICIN") (class "Default")
      (node (ref "J2") (pin "3") (pinfunction "3_3") (pintype "passive"))
      (node (ref "U6") (pin "7") (pinfunction "B4_7") (pintype "bidirectional"))
    )
    (net (code "65") (name "/_I2S_SD") (class "Default")
      (node (ref "J2") (pin "6") (pinfunction "6_6") (pintype "passive"))
      (node (ref "U8") (pin "8") (pinfunction "B3_8") (pintype "bidirectional"))
    )
    (net (code "66") (name "/_I2S_WS") (class "Default")
      (node (ref "J2") (pin "5") (pinfunction "5_5") (pintype "passive"))
      (node (ref "U8") (pin "9") (pinfunction "B2_9") (pintype "bidirectional"))
    )
    (net (code "67") (name "/_JTAG_TCK") (class "Default")
      (node (ref "J1") (pin "18") (pinfunction "18_18") (pintype "passive"))
      (node (ref "U10") (pin "9") (pinfunction "B2_9") (pintype "bidirectional"))
    )
    (net (code "68") (name "/_JTAG_TDI") (class "Default")
      (node (ref "J1") (pin "17") (pinfunction "17_17") (pintype "passive"))
      (node (ref "U10") (pin "8") (pinfunction "B3_8") (pintype "bidirectional"))
    )
    (net (code "69") (name "/_JTAG_TDO") (class "Default")
      (node (ref "J1") (pin "16") (pinfunction "16_16") (pintype "passive"))
      (node (ref "U10") (pin "7") (pinfunction "B4_7") (pintype "bidirectional"))
    )
    (net (code "70") (name "/_JTAG_TMS") (class "Default")
      (node (ref "J1") (pin "19") (pinfunction "19_19") (pintype "passive"))
      (node (ref "U10") (pin "10") (pinfunction "B1_10") (pintype "bidirectional"))
    )
    (net (code "71") (name "/_LED0") (class "Default")
      (node (ref "J1") (pin "6") (pinfunction "6_6") (pintype "passive"))
      (node (ref "U7") (pin "7") (pinfunction "B4_7") (pintype "bidirectional"))
    )
    (net (code "72") (name "/_LED1") (class "Default")
      (node (ref "J1") (pin "7") (pinfunction "7_7") (pintype "passive"))
      (node (ref "U7") (pin "8") (pinfunction "B3_8") (pintype "bidirectional"))
    )
    (net (code "73") (name "/_LED2") (class "Default")
      (node (ref "J1") (pin "8") (pinfunction "8_8") (pintype "passive"))
      (node (ref "U7") (pin "9") (pinfunction "B2_9") (pintype "bidirectional"))
    )
    (net (code "74") (name "/_LED3") (class "Default")
      (node (ref "J1") (pin "9") (pinfunction "9_9") (pintype "passive"))
      (node (ref "U7") (pin "10") (pinfunction "B1_10") (pintype "bidirectional"))
    )
    (net (code "75") (name "/_LED4") (class "Default")
      (node (ref "J1") (pin "10") (pinfunction "10_10") (pintype "passive"))
      (node (ref "U9") (pin "7") (pinfunction "B4_7") (pintype "bidirectional"))
    )
    (net (code "76") (name "/_LED5") (class "Default")
      (node (ref "J1") (pin "11") (pinfunction "11_11") (pintype "passive"))
      (node (ref "U9") (pin "8") (pinfunction "B3_8") (pintype "bidirectional"))
    )
    (net (code "77") (name "/_LED6") (class "Default")
      (node (ref "J1") (pin "12") (pinfunction "12_12") (pintype "passive"))
      (node (ref "U9") (pin "9") (pinfunction "B2_9") (pintype "bidirectional"))
    )
    (net (code "78") (name "/_LED7") (class "Default")
      (node (ref "J1") (pin "13") (pinfunction "13_13") (pintype "passive"))
      (node (ref "U9") (pin "10") (pinfunction "B1_10") (pintype "bidirectional"))
    )
    (net (code "79") (name "/_LED8") (class "Default")
      (node (ref "J1") (pin "14") (pinfunction "14_14") (pintype "passive"))
      (node (ref "U12") (pin "7") (pinfunction "B4_7") (pintype "bidirectional"))
    )
    (net (code "80") (name "/_SPDIF_OUT") (class "Default")
      (node (ref "J2") (pin "2") (pinfunction "2_2") (pintype "passive"))
      (node (ref "U6") (pin "8") (pinfunction "B3_8") (pintype "bidirectional"))
    )
    (net (code "81") (name "/_SPI_CLK") (class "Default")
      (node (ref "J2") (pin "21") (pinfunction "21_21") (pintype "passive"))
      (node (ref "U11") (pin "7") (pinfunction "B4_7") (pintype "bidirectional"))
    )
    (net (code "82") (name "/_SPI_CS") (class "Default")
      (node (ref "J2") (pin "19") (pinfunction "19_19") (pintype "passive"))
      (node (ref "U11") (pin "9") (pinfunction "B2_9") (pintype "bidirectional"))
    )
    (net (code "83") (name "/_SPI_MISO") (class "Default")
      (node (ref "J2") (pin "18") (pinfunction "18_18") (pintype "passive"))
      (node (ref "U11") (pin "10") (pinfunction "B1_10") (pintype "bidirectional"))
    )
    (net (code "84") (name "/_SPI_MOSI") (class "Default")
      (node (ref "J2") (pin "20") (pinfunction "20_20") (pintype "passive"))
      (node (ref "U11") (pin "8") (pinfunction "B3_8") (pintype "bidirectional"))
    )
    (net (code "85") (name "/_UART_CTS") (class "Default")
      (node (ref "J1") (pin "22") (pinfunction "22_22") (pintype "passive"))
      (node (ref "U12") (pin "9") (pinfunction "B2_9") (pintype "bidirectional"))
    )
    (net (code "86") (name "/_UART_RTS") (class "Default")
      (node (ref "J1") (pin "23") (pinfunction "23_23") (pintype "passive"))
      (node (ref "U12") (pin "10") (pinfunction "B1_10") (pintype "bidirectional"))
    )
    (net (code "87") (name "/_UART_RX") (class "Default")
      (node (ref "J1") (pin "3") (pinfunction "3_3") (pintype "passive"))
      (node (ref "U5") (pin "8") (pinfunction "IVCC1_8") (pintype "input"))
    )
    (net (code "88") (name "/_UART_TX") (class "Default")
      (node (ref "J1") (pin "4") (pinfunction "4_4") (pintype "passive"))
      (node (ref "U5") (pin "1") (pinfunction "OVCC2_1") (pintype "output"))
    )
    (net (code "89") (name "/_XLNA") (class "Default")
      (node (ref "J1") (pin "21") (pinfunction "21_21") (pintype "passive"))
      (node (ref "U12") (pin "8") (pinfunction "B3_8") (pintype "bidirectional"))
    )
    (net (code "90") (name "/~{RESET_L}") (class "Default")
      (node (ref "M1") (pin "4") (pinfunction "~{RESET_L}_4") (pintype "input"))
      (node (ref "U13") (pin "5") (pinfunction "A1_5") (pintype "bidirectional"))
    )
    (net (code "91") (name "/~{USB_UART}") (class "Default")
      (node (ref "R4") (pin "2") (pinfunction "2_2") (pintype "passive"))
      (node (ref "U4") (pin "1") (pinfunction "~{OE}_1") (pintype "input"))
      (node (ref "U5") (pin "6") (pinfunction "~{THREE-STATE}_6") (pintype "input"))
      (node (ref "U6") (pin "2") (pinfunction "A1_2") (pintype "bidirectional"))
    )
    (net (code "92") (name "/~{_RESET_L}") (class "Default")
      (node (ref "J1") (pin "25") (pinfunction "25_25") (pintype "passive"))
      (node (ref "U13") (pin "8") (pinfunction "B1_8") (pintype "bidirectional"))
    )
    (net (code "93") (name "/~{_USB_UART}") (class "Default")
      (node (ref "J1") (pin "2") (pinfunction "2_2") (pintype "passive"))
      (node (ref "U6") (pin "10") (pinfunction "B1_10") (pintype "bidirectional"))
    )
    (net (code "94") (name "GND") (class "Default")
      (node (ref "A1") (pin "GND$1") (pinfunction "GND_GND$1") (pintype "power_in"))
      (node (ref "A1") (pin "GND$2") (pinfunction "GND_GND$2") (pintype "power_in"))
      (node (ref "C1") (pin "2") (pinfunction "2_2") (pintype "passive"))
      (node (ref "C10") (pin "2") (pinfunction "2_2") (pintype "passive"))
      (node (ref "C11") (pin "2") (pinfunction "2_2") (pintype "passive"))
      (node (ref "C12") (pin "2") (pinfunction "2_2") (pintype "passive"))
      (node (ref "C13") (pin "2") (pinfunction "2_2") (pintype "passive"))
      (node (ref "C14") (pin "2") (pinfunction "2_2") (pintype "passive"))
      (node (ref "C15") (pin "1") (pinfunction "1_1") (pintype "passive"))
      (node (ref "C16") (pin "2") (pinfunction "2_2") (pintype "passive"))
      (node (ref "C17") (pin "2") (pinfunction "2_2") (pintype "passive"))
      (node (ref "C18") (pin "2") (pinfunction "2_2") (pintype "passive"))
      (node (ref "C19") (pin "2") (pinfunction "2_2") (pintype "passive"))
      (node (ref "C2") (pin "2") (pinfunction "2_2") (pintype "passive"))
      (node (ref "C20") (pin "2") (pinfunction "2_2") (pintype "passive"))
      (node (ref "C21") (pin "2") (pinfunction "2_2") (pintype "passive"))
      (node (ref "C22") (pin "2") (pinfunction "2_2") (pintype "passive"))
      (node (ref "C23") (pin "2") (pinfunction "2_2") (pintype "passive"))
      (node (ref "C24") (pin "1") (pinfunction "1_1") (pintype "passive"))
      (node (ref "C25") (pin "2") (pinfunction "2_2") (pintype "passive"))
      (node (ref "C26") (pin "2") (pinfunction "2_2") (pintype "passive"))
      (node (ref "C27") (pin "1") (pinfunction "1_1") (pintype "passive"))
      (node (ref "C28") (pin "2") (pinfunction "2_2") (pintype "passive"))
      (node (ref "C29") (pin "1") (pinfunction "1_1") (pintype "passive"))
      (node (ref "C3") (pin "2") (pinfunction "2_2") (pintype "passive"))
      (node (ref "C30") (pin "2") (pinfunction "2_2") (pintype "passive"))
      (node (ref "C31") (pin "2") (pinfunction "2_2") (pintype "passive"))
      (node (ref "C32") (pin "2") (pinfunction "2_2") (pintype "passive"))
      (node (ref "C33") (pin "1") (pinfunction "1_1") (pintype "passive"))
      (node (ref "C34") (pin "2") (pinfunction "2_2") (pintype "passive"))
      (node (ref "C35") (pin "1") (pinfunction "1_1") (pintype "passive"))
      (node (ref "C36") (pin "2") (pinfunction "2_2") (pintype "passive"))
      (node (ref "C37") (pin "2") (pinfunction "2_2") (pintype "passive"))
      (node (ref "C38") (pin "1") (pinfunction "1_1") (pintype "passive"))
      (node (ref "C39") (pin "2") (pinfunction "2_2") (pintype "passive"))
      (node (ref "C4") (pin "2") (pinfunction "2_2") (pintype "passive"))
      (node (ref "C40") (pin "2") (pinfunction "2_2") (pintype "passive"))
      (node (ref "C41") (pin "2") (pinfunction "2_2") (pintype "passive"))
      (node (ref "C5") (pin "2") (pinfunction "2_2") (pintype "passive"))
      (node (ref "C6") (pin "2") (pinfunction "2_2") (pintype "passive"))
      (node (ref "C8") (pin "2") (pinfunction "2_2") (pintype "passive"))
      (node (ref "C9") (pin "2") (pinfunction "2_2") (pintype "passive"))
      (node (ref "D2") (pin "1") (pinfunction "P$1_1") (pintype "passive"))
      (node (ref "D3") (pin "1") (pinfunction "C_1") (pintype "passive"))
      (node (ref "D4") (pin "1") (pinfunction "C_1") (pintype "passive"))
      (node (ref "J1") (pin "20") (pinfunction "20_20") (pintype "passive"))
      (node (ref "J1") (pin "5") (pinfunction "5_5") (pintype "passive"))
      (node (ref "J2") (pin "23") (pinfunction "23_23") (pintype "passive"))
      (node (ref "J2") (pin "8") (pinfunction "8_8") (pintype "passive"))
      (node (ref "M1") (pin "1") (pinfunction "GND_1") (pintype "power_in"))
      (node (ref "M1") (pin "10") (pinfunction "GND_10") (pintype "power_in"))
      (node (ref "M1") (pin "2") (pinfunction "GND_2") (pintype "power_in"))
      (node (ref "M1") (pin "22") (pinfunction "GND_22") (pintype "power_in"))
      (node (ref "M1") (pin "27") (pinfunction "GND_27") (pintype "power_in"))
      (node (ref "M1") (pin "3") (pinfunction "GND_3") (pintype "power_in"))
      (node (ref "M1") (pin "35") (pinfunction "GND_35") (pintype "power_in"))
      (node (ref "M1") (pin "45") (pinfunction "GND_45") (pintype "power_in"))
      (node (ref "M1") (pin "51") (pinfunction "GND_51") (pintype "power_in"))
      (node (ref "M1") (pin "54") (pinfunction "GND_54") (pintype "power_in"))
      (node (ref "M1") (pin "57") (pinfunction "GND_57") (pintype "power_in"))
      (node (ref "M1") (pin "58") (pinfunction "GND_58") (pintype "power_in"))
      (node (ref "M1") (pin "60") (pinfunction "GND_60") (pintype "power_in"))
      (node (ref "R11") (pin "1") (pinfunction "1_1") (pintype "passive"))
      (node (ref "R2") (pin "1") (pinfunction "1_1") (pintype "passive"))
      (node (ref "R4") (pin "1") (pinfunction "1_1") (pintype "passive"))
      (node (ref "S1") (pin "5") (pinfunction "5_5") (pintype "passive"))
      (node (ref "U1") (pin "3") (pinfunction "AGND_3") (pintype "power_in"))
      (node (ref "U1") (pin "5") (pinfunction "PGND_5") (pintype "power_in"))
      (node (ref "U10") (pin "6") (pinfunction "GND_6") (pintype "power_in"))
      (node (ref "U11") (pin "6") (pinfunction "GND_6") (pintype "power_in"))
      (node (ref "U12") (pin "6") (pinfunction "GND_6") (pintype "power_in"))
      (node (ref "U13") (pin "2") (pinfunction "GND_2") (pintype "power_in"))
      (node (ref "U2") (pin "2") (pinfunction "GND_2") (pintype "power_in"))
      (node (ref "U3") (pin "2") (pinfunction "GND_2") (pintype "power_in"))
      (node (ref "U3") (pin "PAD") (pinfunction "PAD_PAD") (pintype "power_in"))
      (node (ref "U4") (pin "3") (pinfunction "GND_3") (pintype "power_in"))
      (node (ref "U5") (pin "2") (pinfunction "GND_2") (pintype "power_in"))
      (node (ref "U6") (pin "6") (pinfunction "GND_6") (pintype "power_in"))
      (node (ref "U7") (pin "6") (pinfunction "GND_6") (pintype "power_in"))
      (node (ref "U8") (pin "6") (pinfunction "GND_6") (pintype "power_in"))
      (node (ref "U9") (pin "6") (pinfunction "GND_6") (pintype "power_in"))
    )
    (net (code "95") (name "Net-(D3-A)") (class "Default")
      (node (ref "D3") (pin "2") (pinfunction "A_2") (pintype "passive"))
      (node (ref "R6") (pin "1") (pinfunction "1_1") (pintype "passive"))
    )
    (net (code "96") (name "Net-(D4-A)") (class "Default")
      (node (ref "D4") (pin "2") (pinfunction "A_2") (pintype "passive"))
      (node (ref "R9") (pin "1") (pinfunction "1_1") (pintype "passive"))
    )
    (net (code "97") (name "Net-(M1-+2.5VD_OUT)") (class "Default")
      (node (ref "M1") (pin "23") (pinfunction "+2.5VD_OUT_23") (pintype "power_in"))
      (node (ref "R8") (pin "2") (pinfunction "2_2") (pintype "passive"))
    )
    (net (code "98") (name "Net-(M1-+3.3VD_IN-Pad25)") (class "Default")
      (node (ref "M1") (pin "25") (pinfunction "+3.3VD_IN_25") (pintype "power_in"))
      (node (ref "M1") (pin "26") (pinfunction "+3.3VD_IN_26") (pintype "power_in"))
      (node (ref "R6") (pin "2") (pinfunction "2_2") (pintype "passive"))
      (node (ref "R7") (pin "2") (pinfunction "2_2") (pintype "passive"))
    )
    (net (code "99") (name "Net-(TP1-PP)") (class "Default")
      (node (ref "TP1") (pin "1") (pinfunction "PP_1") (pintype "passive"))
      (node (ref "U3") (pin "1") (pinfunction "RI_1") (pintype "input"))
    )
    (net (code "100") (name "Net-(TP3-PP)") (class "Default")
      (node (ref "TP3") (pin "1") (pinfunction "PP_1") (pintype "passive"))
      (node (ref "U3") (pin "11") (pinfunction "GPIO.3_11") (pintype "bidirectional"))
    )
    (net (code "101") (name "Net-(TP4-PP)") (class "Default")
      (node (ref "TP4") (pin "1") (pinfunction "PP_1") (pintype "passive"))
      (node (ref "U3") (pin "12") (pinfunction "GPIO.2_12") (pintype "bidirectional"))
    )
    (net (code "102") (name "Net-(TP5-PP)") (class "Default")
      (node (ref "TP5") (pin "1") (pinfunction "PP_1") (pintype "passive"))
      (node (ref "U3") (pin "13") (pinfunction "GPIO.1_13") (pintype "bidirectional"))
    )
    (net (code "103") (name "Net-(TP6-PP)") (class "Default")
      (node (ref "TP6") (pin "1") (pinfunction "PP_1") (pintype "passive"))
      (node (ref "U3") (pin "14") (pinfunction "GPIO.0_14") (pintype "bidirectional"))
    )
    (net (code "104") (name "Net-(TP7-PP)") (class "Default")
      (node (ref "TP7") (pin "1") (pinfunction "PP_1") (pintype "passive"))
      (node (ref "U3") (pin "18") (pinfunction "CTS_18") (pintype "input"))
    )
    (net (code "105") (name "Net-(TP8-PP)") (class "Default")
      (node (ref "TP8") (pin "1") (pinfunction "PP_1") (pintype "passive"))
      (node (ref "U3") (pin "19") (pinfunction "RTS_19") (pintype "output"))
    )
    (net (code "106") (name "Net-(TP10-PP)") (class "Default")
      (node (ref "TP10") (pin "1") (pinfunction "PP_1") (pintype "passive"))
      (node (ref "U3") (pin "23") (pinfunction "DTR_23") (pintype "output"))
    )
    (net (code "107") (name "Net-(TP11-PP)") (class "Default")
      (node (ref "TP11") (pin "1") (pinfunction "PP_1") (pintype "passive"))
      (node (ref "U3") (pin "24") (pinfunction "DCD_24") (pintype "input"))
    )
    (net (code "108") (name "Net-(U3-VDD)") (class "Default")
      (node (ref "C8") (pin "1") (pinfunction "1_1") (pintype "passive"))
      (node (ref "C9") (pin "1") (pinfunction "1_1") (pintype "passive"))
      (node (ref "U3") (pin "6") (pinfunction "VDD_6") (pintype "power_in"))
    )
    (net (code "109") (name "Net-(U3-VPP)") (class "Default")
      (node (ref "C20") (pin "1") (pinfunction "1_1") (pintype "passive"))
      (node (ref "U3") (pin "16") (pinfunction "VPP_16") (pintype "passive"))
    )
    (net (code "110") (name "PE") (class "Default")
      (node (ref "C1") (pin "1") (pinfunction "1_1") (pintype "passive"))
      (node (ref "S1") (pin "S$1") (pinfunction "M0_S$1") (pintype "passive"))
      (node (ref "S1") (pin "S$2") (pinfunction "M1_S$2") (pintype "passive"))
      (node (ref "S1") (pin "S$3") (pinfunction "M2_S$3") (pintype "passive"))
    )
    (net (code "111") (name "unconnected-(S1-Pad4)") (class "Default")
      (node (ref "S1") (pin "4") (pinfunction "4_4") (pintype "passive"))
    )
    (net (code "112") (name "unconnected-(SW1-Pad2)") (class "Default")
      (node (ref "SW1") (pin "2") (pinfunction "2_2") (pintype "passive"))
    )
    (net (code "113") (name "unconnected-(SW1-Pad4)") (class "Default")
      (node (ref "SW1") (pin "4") (pinfunction "4_4") (pintype "passive"))
    )
    (net (code "114") (name "unconnected-(U1-PG-Pad8)") (class "Default")
      (node (ref "U1") (pin "8") (pinfunction "PG_8") (pintype "open_collector"))
    )
    (net (code "115") (name "unconnected-(U2-NC-Pad4)") (class "Default")
      (node (ref "U2") (pin "4") (pinfunction "NC_4") (pintype "no_connect"))
    )
    (net (code "116") (name "unconnected-(U3-DSR-Pad22)") (class "Default")
      (node (ref "U3") (pin "22") (pinfunction "DSR_22") (pintype "input"))
    )
    (net (code "117") (name "unconnected-(U3-NC-Pad10)") (class "Default")
      (node (ref "U3") (pin "10") (pinfunction "NC_10") (pintype "no_connect"))
    )
    (net (code "118") (name "unconnected-(U3-SUSPEND-Pad17)") (class "Default")
      (node (ref "U3") (pin "17") (pinfunction "SUSPEND_17") (pintype "output"))
    )
    (net (code "119") (name "unconnected-(U3-~{RST}-Pad9)") (class "Default")
      (node (ref "U3") (pin "9") (pinfunction "~{RST}_9") (pintype "bidirectional"))
    )
    (net (code "120") (name "unconnected-(U3-~{SUSPEND}-Pad15)") (class "Default")
      (node (ref "U3") (pin "15") (pinfunction "~{SUSPEND}_15") (pintype "output"))
    )
  )
)
